# SCH_TrafficLight.net
KiCad netlist of a schematic drawn in Altium Designer
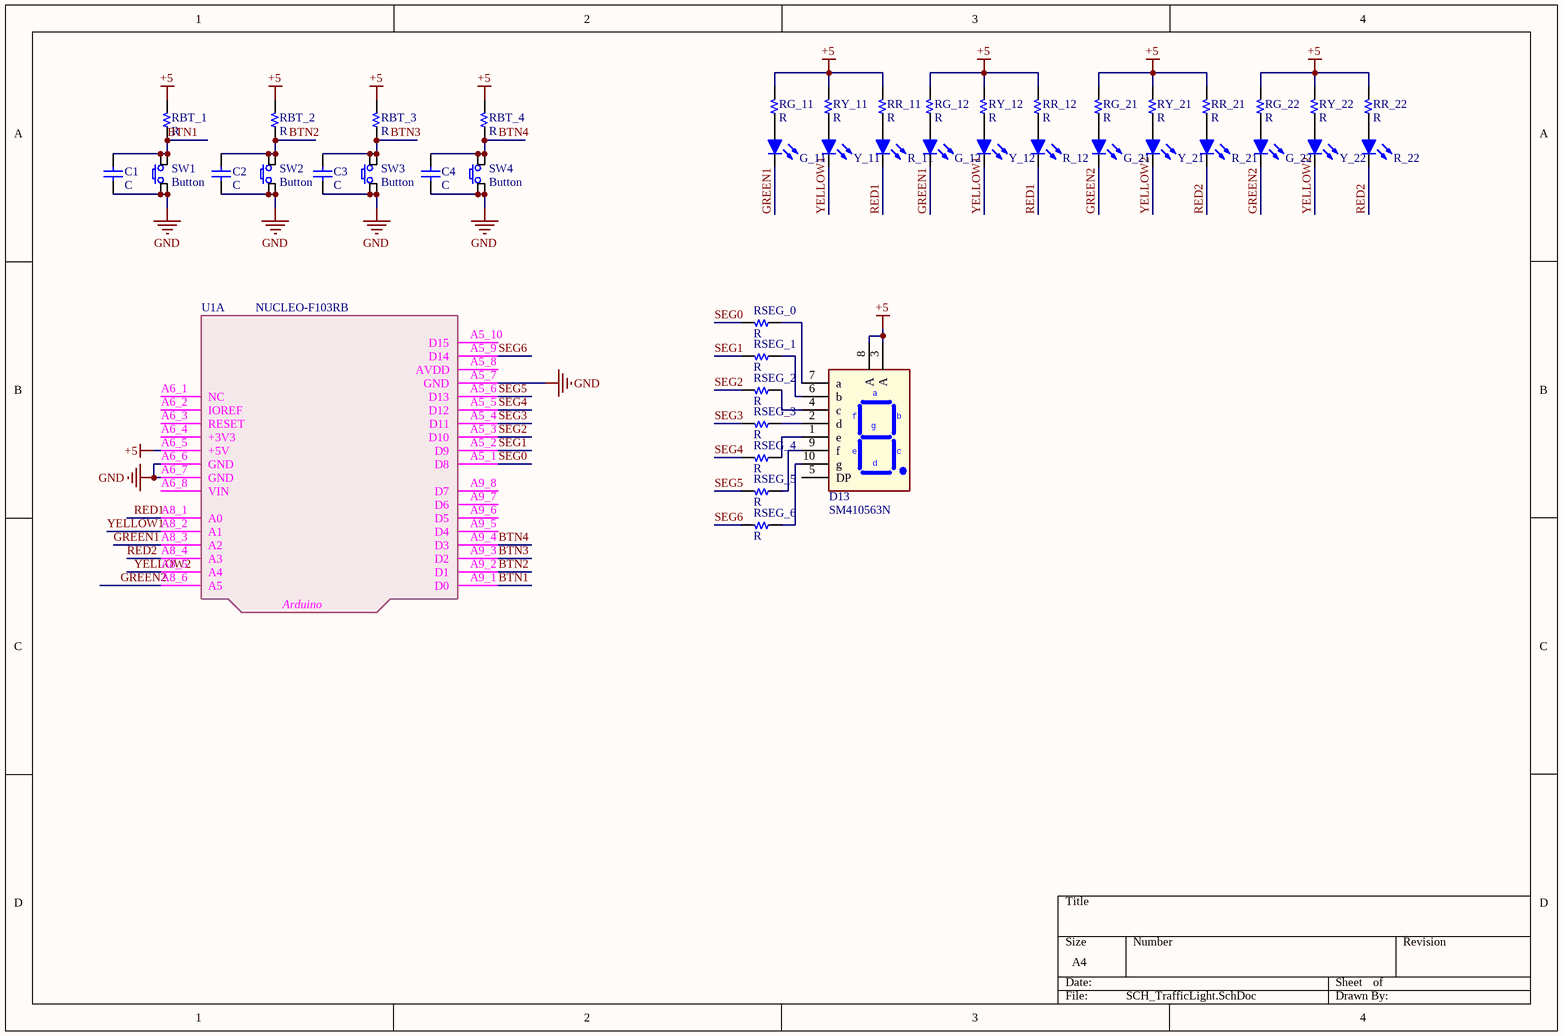
[diagram p0: SCH_TrafficLight.SchDoc]

(export (version "E")
  (design (tool "Eeschema 10.0.6"))
  (components
    (comp (ref "C1")
      (value "C")
      (footprint "C 0805")
      (description "Capacitor non-pol")
      (libsource (lib "chipfc_libs") (part "Capacitor NP"))
    )
    (comp (ref "C2")
      (value "C")
      (footprint "C 0805")
      (description "Capacitor non-pol")
      (libsource (lib "chipfc_libs") (part "Capacitor NP"))
    )
    (comp (ref "C3")
      (value "C")
      (footprint "C 0805")
      (description "Capacitor non-pol")
      (libsource (lib "chipfc_libs") (part "Capacitor NP"))
    )
    (comp (ref "C4")
      (value "C")
      (footprint "C 0805")
      (description "Capacitor non-pol")
      (libsource (lib "chipfc_libs") (part "Capacitor NP"))
    )
    (comp (ref "D13")
      (value "SM410563N")
      (footprint "LED/7SEG/0.56")
      (description "SM410563N, Common-Anode, LED 7-seg, RED, 0.56\",")
      (libsource (lib "led") (part "LED 7-SEG SM410563N"))
    )
    (comp (ref "G_11")
      (value "Led")
      (footprint "LED 3MM - green")
      (description "Typical LED")
      (libsource (lib "led") (part "Led"))
    )
    (comp (ref "G_12")
      (value "Led")
      (footprint "LED 3MM - green")
      (description "Typical LED")
      (libsource (lib "led") (part "Led"))
    )
    (comp (ref "G_21")
      (value "Led")
      (footprint "LED 3MM - green")
      (description "Typical LED")
      (libsource (lib "led") (part "Led"))
    )
    (comp (ref "G_22")
      (value "Led")
      (footprint "LED 3MM - green")
      (description "Typical LED")
      (libsource (lib "led") (part "Led"))
    )
    (comp (ref "RBT_1")
      (value "R")
      (footprint "R 0805")
      (description "Resistor")
      (libsource (lib "chipfc_libs") (part "Resistor"))
    )
    (comp (ref "RBT_2")
      (value "R")
      (footprint "R 0805")
      (description "Resistor")
      (libsource (lib "chipfc_libs") (part "Resistor"))
    )
    (comp (ref "RBT_3")
      (value "R")
      (footprint "R 0805")
      (description "Resistor")
      (libsource (lib "chipfc_libs") (part "Resistor"))
    )
    (comp (ref "RBT_4")
      (value "R")
      (footprint "R 0805")
      (description "Resistor")
      (libsource (lib "chipfc_libs") (part "Resistor"))
    )
    (comp (ref "RG_11")
      (value "R")
      (footprint "R 0805")
      (description "Resistor")
      (libsource (lib "chipfc_libs") (part "Resistor"))
    )
    (comp (ref "RG_12")
      (value "R")
      (footprint "R 0805")
      (description "Resistor")
      (libsource (lib "chipfc_libs") (part "Resistor"))
    )
    (comp (ref "RG_21")
      (value "R")
      (footprint "R 0805")
      (description "Resistor")
      (libsource (lib "chipfc_libs") (part "Resistor"))
    )
    (comp (ref "RG_22")
      (value "R")
      (footprint "R 0805")
      (description "Resistor")
      (libsource (lib "chipfc_libs") (part "Resistor"))
    )
    (comp (ref "RR_11")
      (value "R")
      (footprint "R 0805")
      (description "Resistor")
      (libsource (lib "chipfc_libs") (part "Resistor"))
    )
    (comp (ref "RR_12")
      (value "R")
      (footprint "R 0805")
      (description "Resistor")
      (libsource (lib "chipfc_libs") (part "Resistor"))
    )
    (comp (ref "RR_21")
      (value "R")
      (footprint "R 0805")
      (description "Resistor")
      (libsource (lib "chipfc_libs") (part "Resistor"))
    )
    (comp (ref "RR_22")
      (value "R")
      (footprint "R 0805")
      (description "Resistor")
      (libsource (lib "chipfc_libs") (part "Resistor"))
    )
    (comp (ref "RSEG_0")
      (value "R")
      (footprint "R 0805")
      (description "Resistor")
      (libsource (lib "chipfc_libs") (part "Resistor"))
    )
    (comp (ref "RSEG_1")
      (value "R")
      (footprint "R 0805")
      (description "Resistor")
      (libsource (lib "chipfc_libs") (part "Resistor"))
    )
    (comp (ref "RSEG_2")
      (value "R")
      (footprint "R 0805")
      (description "Resistor")
      (libsource (lib "chipfc_libs") (part "Resistor"))
    )
    (comp (ref "RSEG_3")
      (value "R")
      (footprint "R 0805")
      (description "Resistor")
      (libsource (lib "chipfc_libs") (part "Resistor"))
    )
    (comp (ref "RSEG_4")
      (value "R")
      (footprint "R 0805")
      (description "Resistor")
      (libsource (lib "chipfc_libs") (part "Resistor"))
    )
    (comp (ref "RSEG_5")
      (value "R")
      (footprint "R 0805")
      (description "Resistor")
      (libsource (lib "chipfc_libs") (part "Resistor"))
    )
    (comp (ref "RSEG_6")
      (value "R")
      (footprint "R 0805")
      (description "Resistor")
      (libsource (lib "chipfc_libs") (part "Resistor"))
    )
    (comp (ref "RY_11")
      (value "R")
      (footprint "R 0805")
      (description "Resistor")
      (libsource (lib "chipfc_libs") (part "Resistor"))
    )
    (comp (ref "RY_12")
      (value "R")
      (footprint "R 0805")
      (description "Resistor")
      (libsource (lib "chipfc_libs") (part "Resistor"))
    )
    (comp (ref "RY_21")
      (value "R")
      (footprint "R 0805")
      (description "Resistor")
      (libsource (lib "chipfc_libs") (part "Resistor"))
    )
    (comp (ref "RY_22")
      (value "R")
      (footprint "R 0805")
      (description "Resistor")
      (libsource (lib "chipfc_libs") (part "Resistor"))
    )
    (comp (ref "R_11")
      (value "Led")
      (footprint "LED 3MM - red")
      (description "Typical LED")
      (libsource (lib "led") (part "Led"))
    )
    (comp (ref "R_12")
      (value "Led")
      (footprint "LED 3MM - red")
      (description "Typical LED")
      (libsource (lib "led") (part "Led"))
    )
    (comp (ref "R_21")
      (value "Led")
      (footprint "LED 3MM - red")
      (description "Typical LED")
      (libsource (lib "led") (part "Led"))
    )
    (comp (ref "R_22")
      (value "Led")
      (footprint "LED 3MM - red")
      (description "Typical LED")
      (libsource (lib "led") (part "Led"))
    )
    (comp (ref "SW1")
      (value "Button")
      (footprint "SW/4/06MM")
      (description "Tact switch 4-pin")
      (libsource (lib "bs_libs") (part "SW SPST 4-pin"))
    )
    (comp (ref "SW2")
      (value "Button")
      (footprint "SW/4/06MM")
      (description "Tact switch 4-pin")
      (libsource (lib "bs_libs") (part "SW SPST 4-pin"))
    )
    (comp (ref "SW3")
      (value "Button")
      (footprint "SW/4/06MM")
      (description "Tact switch 4-pin")
      (libsource (lib "bs_libs") (part "SW SPST 4-pin"))
    )
    (comp (ref "SW4")
      (value "Button")
      (footprint "SW/4/06MM")
      (description "Tact switch 4-pin")
      (libsource (lib "bs_libs") (part "SW SPST 4-pin"))
    )
    (comp (ref "U1")
      (value "NUCLEO-F103RB")
      (footprint "NUCLEO")
      (fields (field (name "MANUFACTURER") "STMicroelectronics"))
      (libsource (lib "nucleo") (part "NUCLEO-F103RB"))
    )
    (comp (ref "Y_11")
      (value "Led")
      (footprint "LED 3MM - yellow")
      (description "Typical LED")
      (libsource (lib "led") (part "Led"))
    )
    (comp (ref "Y_12")
      (value "Led")
      (footprint "LED 3MM - yellow")
      (description "Typical LED")
      (libsource (lib "led") (part "Led"))
    )
    (comp (ref "Y_21")
      (value "Led")
      (footprint "LED 3MM - yellow")
      (description "Typical LED")
      (libsource (lib "led") (part "Led"))
    )
    (comp (ref "Y_22")
      (value "Led")
      (footprint "LED 3MM - yellow")
      (description "Typical LED")
      (libsource (lib "led") (part "Led"))
    )
  )
  (nets
    (net (code "1") (name "+5") (class "Default")
      (node (ref "D13") (pin "3") (pinfunction "A_3") (pintype "passive"))
      (node (ref "D13") (pin "8") (pinfunction "A_8") (pintype "passive"))
      (node (ref "RBT_1") (pin "2") (pinfunction "2_2") (pintype "passive"))
      (node (ref "RBT_2") (pin "2") (pinfunction "2_2") (pintype "passive"))
      (node (ref "RBT_3") (pin "2") (pinfunction "2_2") (pintype "passive"))
      (node (ref "RBT_4") (pin "2") (pinfunction "2_2") (pintype "passive"))
      (node (ref "RG_11") (pin "2") (pinfunction "2_2") (pintype "passive"))
      (node (ref "RG_12") (pin "2") (pinfunction "2_2") (pintype "passive"))
      (node (ref "RG_21") (pin "2") (pinfunction "2_2") (pintype "passive"))
      (node (ref "RG_22") (pin "2") (pinfunction "2_2") (pintype "passive"))
      (node (ref "RR_11") (pin "2") (pinfunction "2_2") (pintype "passive"))
      (node (ref "RR_12") (pin "2") (pinfunction "2_2") (pintype "passive"))
      (node (ref "RR_21") (pin "2") (pinfunction "2_2") (pintype "passive"))
      (node (ref "RR_22") (pin "2") (pinfunction "2_2") (pintype "passive"))
      (node (ref "RY_11") (pin "2") (pinfunction "2_2") (pintype "passive"))
      (node (ref "RY_12") (pin "2") (pinfunction "2_2") (pintype "passive"))
      (node (ref "RY_21") (pin "2") (pinfunction "2_2") (pintype "passive"))
      (node (ref "RY_22") (pin "2") (pinfunction "2_2") (pintype "passive"))
      (node (ref "U1") (pin "A6_5") (pinfunction "+5V_A6_5") (pintype "passive"))
    )
    (net (code "2") (name "/BTN1") (class "Default")
      (node (ref "C1") (pin "1") (pinfunction "1_1") (pintype "passive"))
      (node (ref "RBT_1") (pin "1") (pinfunction "1_1") (pintype "passive"))
      (node (ref "SW1") (pin "3") (pinfunction "3_3") (pintype "passive"))
      (node (ref "SW1") (pin "4") (pinfunction "4_4") (pintype "passive"))
      (node (ref "U1") (pin "A9_1") (pinfunction "D0_A9_1") (pintype "passive"))
    )
    (net (code "3") (name "/BTN2") (class "Default")
      (node (ref "C2") (pin "1") (pinfunction "1_1") (pintype "passive"))
      (node (ref "RBT_2") (pin "1") (pinfunction "1_1") (pintype "passive"))
      (node (ref "SW2") (pin "3") (pinfunction "3_3") (pintype "passive"))
      (node (ref "SW2") (pin "4") (pinfunction "4_4") (pintype "passive"))
      (node (ref "U1") (pin "A9_2") (pinfunction "D1_A9_2") (pintype "passive"))
    )
    (net (code "4") (name "/BTN3") (class "Default")
      (node (ref "C3") (pin "1") (pinfunction "1_1") (pintype "passive"))
      (node (ref "RBT_3") (pin "1") (pinfunction "1_1") (pintype "passive"))
      (node (ref "SW3") (pin "3") (pinfunction "3_3") (pintype "passive"))
      (node (ref "SW3") (pin "4") (pinfunction "4_4") (pintype "passive"))
      (node (ref "U1") (pin "A9_3") (pinfunction "D2_A9_3") (pintype "passive"))
    )
    (net (code "5") (name "/BTN4") (class "Default")
      (node (ref "C4") (pin "1") (pinfunction "1_1") (pintype "passive"))
      (node (ref "RBT_4") (pin "1") (pinfunction "1_1") (pintype "passive"))
      (node (ref "SW4") (pin "3") (pinfunction "3_3") (pintype "passive"))
      (node (ref "SW4") (pin "4") (pinfunction "4_4") (pintype "passive"))
      (node (ref "U1") (pin "A9_4") (pinfunction "D3_A9_4") (pintype "passive"))
    )
    (net (code "6") (name "/GREEN1") (class "Default")
      (node (ref "G_11") (pin "2") (pinfunction "K_2") (pintype "passive"))
      (node (ref "G_12") (pin "2") (pinfunction "K_2") (pintype "passive"))
      (node (ref "U1") (pin "A8_3") (pinfunction "A2_A8_3") (pintype "passive"))
    )
    (net (code "7") (name "/GREEN2") (class "Default")
      (node (ref "G_21") (pin "2") (pinfunction "K_2") (pintype "passive"))
      (node (ref "G_22") (pin "2") (pinfunction "K_2") (pintype "passive"))
      (node (ref "U1") (pin "A8_6") (pinfunction "A5_A8_6") (pintype "passive"))
    )
    (net (code "8") (name "/RED1") (class "Default")
      (node (ref "R_11") (pin "2") (pinfunction "K_2") (pintype "passive"))
      (node (ref "R_12") (pin "2") (pinfunction "K_2") (pintype "passive"))
      (node (ref "U1") (pin "A8_1") (pinfunction "A0_A8_1") (pintype "passive"))
    )
    (net (code "9") (name "/RED2") (class "Default")
      (node (ref "R_21") (pin "2") (pinfunction "K_2") (pintype "passive"))
      (node (ref "R_22") (pin "2") (pinfunction "K_2") (pintype "passive"))
      (node (ref "U1") (pin "A8_4") (pinfunction "A3_A8_4") (pintype "passive"))
    )
    (net (code "10") (name "/SEG0") (class "Default")
      (node (ref "RSEG_0") (pin "2") (pinfunction "2_2") (pintype "passive"))
      (node (ref "U1") (pin "A5_1") (pinfunction "D8_A5_1") (pintype "passive"))
    )
    (net (code "11") (name "/SEG1") (class "Default")
      (node (ref "RSEG_1") (pin "2") (pinfunction "2_2") (pintype "passive"))
      (node (ref "U1") (pin "A5_2") (pinfunction "D9_A5_2") (pintype "passive"))
    )
    (net (code "12") (name "/SEG2") (class "Default")
      (node (ref "RSEG_2") (pin "2") (pinfunction "2_2") (pintype "passive"))
      (node (ref "U1") (pin "A5_3") (pinfunction "D10_A5_3") (pintype "passive"))
    )
    (net (code "13") (name "/SEG3") (class "Default")
      (node (ref "RSEG_3") (pin "2") (pinfunction "2_2") (pintype "passive"))
      (node (ref "U1") (pin "A5_4") (pinfunction "D11_A5_4") (pintype "passive"))
    )
    (net (code "14") (name "/SEG4") (class "Default")
      (node (ref "RSEG_4") (pin "2") (pinfunction "2_2") (pintype "passive"))
      (node (ref "U1") (pin "A5_5") (pinfunction "D12_A5_5") (pintype "passive"))
    )
    (net (code "15") (name "/SEG5") (class "Default")
      (node (ref "RSEG_5") (pin "2") (pinfunction "2_2") (pintype "passive"))
      (node (ref "U1") (pin "A5_6") (pinfunction "D13_A5_6") (pintype "passive"))
    )
    (net (code "16") (name "/SEG6") (class "Default")
      (node (ref "RSEG_6") (pin "2") (pinfunction "2_2") (pintype "passive"))
      (node (ref "U1") (pin "A5_9") (pinfunction "D14_A5_9") (pintype "passive"))
    )
    (net (code "17") (name "/YELLOW1") (class "Default")
      (node (ref "U1") (pin "A8_2") (pinfunction "A1_A8_2") (pintype "passive"))
      (node (ref "Y_11") (pin "2") (pinfunction "K_2") (pintype "passive"))
      (node (ref "Y_12") (pin "2") (pinfunction "K_2") (pintype "passive"))
    )
    (net (code "18") (name "/YELLOW2") (class "Default")
      (node (ref "U1") (pin "A8_5") (pinfunction "A4_A8_5") (pintype "passive"))
      (node (ref "Y_21") (pin "2") (pinfunction "K_2") (pintype "passive"))
      (node (ref "Y_22") (pin "2") (pinfunction "K_2") (pintype "passive"))
    )
    (net (code "19") (name "GND") (class "Default")
      (node (ref "C1") (pin "2") (pinfunction "2_2") (pintype "passive"))
      (node (ref "C2") (pin "2") (pinfunction "2_2") (pintype "passive"))
      (node (ref "C3") (pin "2") (pinfunction "2_2") (pintype "passive"))
      (node (ref "C4") (pin "2") (pinfunction "2_2") (pintype "passive"))
      (node (ref "SW1") (pin "1") (pinfunction "1_1") (pintype "passive"))
      (node (ref "SW1") (pin "2") (pinfunction "2_2") (pintype "passive"))
      (node (ref "SW2") (pin "1") (pinfunction "1_1") (pintype "passive"))
      (node (ref "SW2") (pin "2") (pinfunction "2_2") (pintype "passive"))
      (node (ref "SW3") (pin "1") (pinfunction "1_1") (pintype "passive"))
      (node (ref "SW3") (pin "2") (pinfunction "2_2") (pintype "passive"))
      (node (ref "SW4") (pin "1") (pinfunction "1_1") (pintype "passive"))
      (node (ref "SW4") (pin "2") (pinfunction "2_2") (pintype "passive"))
      (node (ref "U1") (pin "A5_7") (pinfunction "GND_A5_7") (pintype "passive"))
      (node (ref "U1") (pin "A6_6") (pinfunction "GND_A6_6") (pintype "passive"))
      (node (ref "U1") (pin "A6_7") (pinfunction "GND_A6_7") (pintype "passive"))
    )
    (net (code "20") (name "Net-(D13-a)") (class "Default")
      (node (ref "D13") (pin "7") (pinfunction "a_7") (pintype "passive"))
      (node (ref "RSEG_0") (pin "1") (pinfunction "1_1") (pintype "passive"))
    )
    (net (code "21") (name "Net-(D13-b)") (class "Default")
      (node (ref "D13") (pin "6") (pinfunction "b_6") (pintype "passive"))
      (node (ref "RSEG_1") (pin "1") (pinfunction "1_1") (pintype "passive"))
    )
    (net (code "22") (name "Net-(D13-c)") (class "Default")
      (node (ref "D13") (pin "4") (pinfunction "c_4") (pintype "passive"))
      (node (ref "RSEG_2") (pin "1") (pinfunction "1_1") (pintype "passive"))
    )
    (net (code "23") (name "Net-(D13-d)") (class "Default")
      (node (ref "D13") (pin "2") (pinfunction "d_2") (pintype "passive"))
      (node (ref "RSEG_3") (pin "1") (pinfunction "1_1") (pintype "passive"))
    )
    (net (code "24") (name "Net-(D13-e)") (class "Default")
      (node (ref "D13") (pin "1") (pinfunction "e_1") (pintype "passive"))
      (node (ref "RSEG_4") (pin "1") (pinfunction "1_1") (pintype "passive"))
    )
    (net (code "25") (name "Net-(D13-f)") (class "Default")
      (node (ref "D13") (pin "9") (pinfunction "f_9") (pintype "passive"))
      (node (ref "RSEG_5") (pin "1") (pinfunction "1_1") (pintype "passive"))
    )
    (net (code "26") (name "Net-(D13-g)") (class "Default")
      (node (ref "D13") (pin "10") (pinfunction "g_10") (pintype "passive"))
      (node (ref "RSEG_6") (pin "1") (pinfunction "1_1") (pintype "passive"))
    )
    (net (code "27") (name "Net-(G_11-A)") (class "Default")
      (node (ref "G_11") (pin "1") (pinfunction "A_1") (pintype "passive"))
      (node (ref "RG_11") (pin "1") (pinfunction "1_1") (pintype "passive"))
    )
    (net (code "28") (name "Net-(G_12-A)") (class "Default")
      (node (ref "G_12") (pin "1") (pinfunction "A_1") (pintype "passive"))
      (node (ref "RG_12") (pin "1") (pinfunction "1_1") (pintype "passive"))
    )
    (net (code "29") (name "Net-(G_21-A)") (class "Default")
      (node (ref "G_21") (pin "1") (pinfunction "A_1") (pintype "passive"))
      (node (ref "RG_21") (pin "1") (pinfunction "1_1") (pintype "passive"))
    )
    (net (code "30") (name "Net-(G_22-A)") (class "Default")
      (node (ref "G_22") (pin "1") (pinfunction "A_1") (pintype "passive"))
      (node (ref "RG_22") (pin "1") (pinfunction "1_1") (pintype "passive"))
    )
    (net (code "31") (name "Net-(R_11-A)") (class "Default")
      (node (ref "RR_11") (pin "1") (pinfunction "1_1") (pintype "passive"))
      (node (ref "R_11") (pin "1") (pinfunction "A_1") (pintype "passive"))
    )
    (net (code "32") (name "Net-(R_12-A)") (class "Default")
      (node (ref "RR_12") (pin "1") (pinfunction "1_1") (pintype "passive"))
      (node (ref "R_12") (pin "1") (pinfunction "A_1") (pintype "passive"))
    )
    (net (code "33") (name "Net-(R_21-A)") (class "Default")
      (node (ref "RR_21") (pin "1") (pinfunction "1_1") (pintype "passive"))
      (node (ref "R_21") (pin "1") (pinfunction "A_1") (pintype "passive"))
    )
    (net (code "34") (name "Net-(R_22-A)") (class "Default")
      (node (ref "RR_22") (pin "1") (pinfunction "1_1") (pintype "passive"))
      (node (ref "R_22") (pin "1") (pinfunction "A_1") (pintype "passive"))
    )
    (net (code "35") (name "Net-(Y_11-A)") (class "Default")
      (node (ref "RY_11") (pin "1") (pinfunction "1_1") (pintype "passive"))
      (node (ref "Y_11") (pin "1") (pinfunction "A_1") (pintype "passive"))
    )
    (net (code "36") (name "Net-(Y_12-A)") (class "Default")
      (node (ref "RY_12") (pin "1") (pinfunction "1_1") (pintype "passive"))
      (node (ref "Y_12") (pin "1") (pinfunction "A_1") (pintype "passive"))
    )
    (net (code "37") (name "Net-(Y_21-A)") (class "Default")
      (node (ref "RY_21") (pin "1") (pinfunction "1_1") (pintype "passive"))
      (node (ref "Y_21") (pin "1") (pinfunction "A_1") (pintype "passive"))
    )
    (net (code "38") (name "Net-(Y_22-A)") (class "Default")
      (node (ref "RY_22") (pin "1") (pinfunction "1_1") (pintype "passive"))
      (node (ref "Y_22") (pin "1") (pinfunction "A_1") (pintype "passive"))
    )
    (net (code "39") (name "unconnected-(D13-DP-Pad5)") (class "Default")
      (node (ref "D13") (pin "5") (pinfunction "DP_5") (pintype "passive"))
    )
    (net (code "40") (name "unconnected-(U1A-+3V3-PadA6_4)") (class "Default")
      (node (ref "U1") (pin "A6_4") (pinfunction "+3V3_A6_4") (pintype "passive"))
    )
    (net (code "41") (name "unconnected-(U1A-AVDD-PadA5_8)") (class "Default")
      (node (ref "U1") (pin "A5_8") (pinfunction "AVDD_A5_8") (pintype "passive"))
    )
    (net (code "42") (name "unconnected-(U1A-D4-PadA9_5)") (class "Default")
      (node (ref "U1") (pin "A9_5") (pinfunction "D4_A9_5") (pintype "passive"))
    )
    (net (code "43") (name "unconnected-(U1A-D5-PadA9_6)") (class "Default")
      (node (ref "U1") (pin "A9_6") (pinfunction "D5_A9_6") (pintype "passive"))
    )
    (net (code "44") (name "unconnected-(U1A-D6-PadA9_7)") (class "Default")
      (node (ref "U1") (pin "A9_7") (pinfunction "D6_A9_7") (pintype "passive"))
    )
    (net (code "45") (name "unconnected-(U1A-D7-PadA9_8)") (class "Default")
      (node (ref "U1") (pin "A9_8") (pinfunction "D7_A9_8") (pintype "passive"))
    )
    (net (code "46") (name "unconnected-(U1A-D15-PadA5_10)") (class "Default")
      (node (ref "U1") (pin "A5_10") (pinfunction "D15_A5_10") (pintype "passive"))
    )
    (net (code "47") (name "unconnected-(U1A-IOREF-PadA6_2)") (class "Default")
      (node (ref "U1") (pin "A6_2") (pinfunction "IOREF_A6_2") (pintype "passive"))
    )
    (net (code "48") (name "unconnected-(U1A-NC-PadA6_1)") (class "Default")
      (node (ref "U1") (pin "A6_1") (pinfunction "NC_A6_1") (pintype "passive"))
    )
    (net (code "49") (name "unconnected-(U1A-RESET-PadA6_3)") (class "Default")
      (node (ref "U1") (pin "A6_3") (pinfunction "RESET_A6_3") (pintype "passive"))
    )
    (net (code "50") (name "unconnected-(U1A-VIN-PadA6_8)") (class "Default")
      (node (ref "U1") (pin "A6_8") (pinfunction "VIN_A6_8") (pintype "passive"))
    )
  )
)
